# sensor_to_raspi.net
KiCad netlist of a schematic drawn in EAGLE
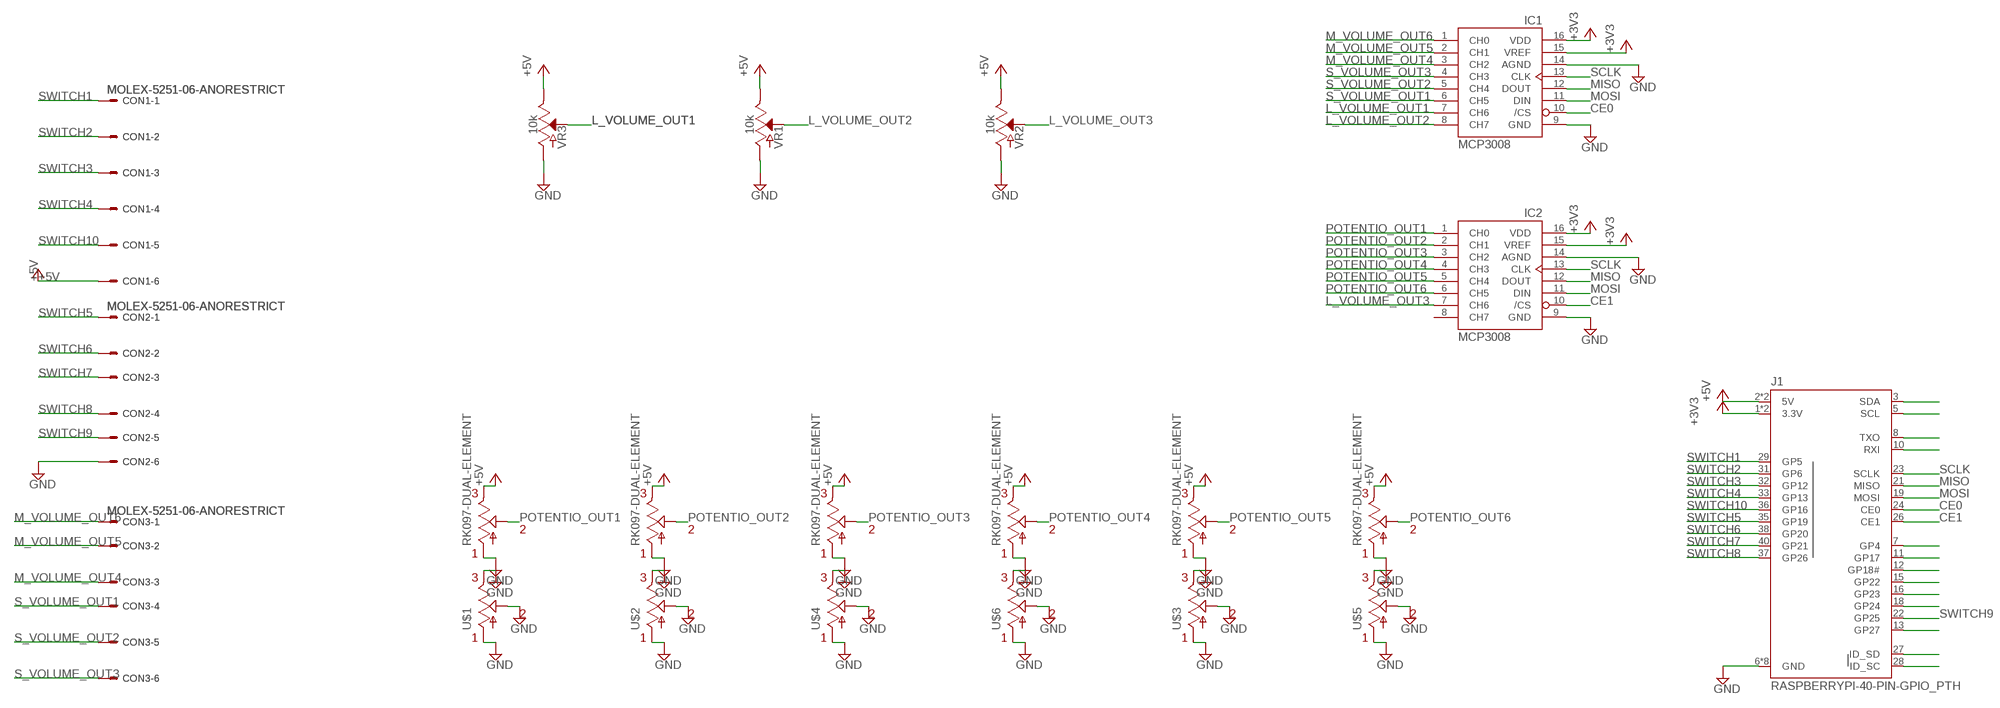
[diagram p0: schematic, sheet 1]

(export (version "E")
  (design (tool "Eeschema 10.0.6"))
  (components
    (comp (ref "CON1")
      (value "MOLEX-5251-06-ANORESTRICT")
      (footprint "eagle-import:5251-06-ANORESTRICT")
      (libsource (lib "eagle-import") (part "MOLEX-5251-06-ANORESTRICT"))
    )
    (comp (ref "CON2")
      (value "MOLEX-5251-06-ANORESTRICT")
      (footprint "eagle-import:5251-06-ANORESTRICT")
      (libsource (lib "eagle-import") (part "MOLEX-5251-06-ANORESTRICT"))
    )
    (comp (ref "CON3")
      (value "MOLEX-5251-06-ANORESTRICT")
      (footprint "eagle-import:5251-06-ANORESTRICT")
      (libsource (lib "eagle-import") (part "MOLEX-5251-06-ANORESTRICT"))
    )
    (comp (ref "IC1")
      (value "MCP3008")
      (footprint "eagle-import:DIL16")
      (libsource (lib "eagle-import") (part "MCP3008"))
    )
    (comp (ref "IC2")
      (value "MCP3008")
      (footprint "eagle-import:DIL16")
      (libsource (lib "eagle-import") (part "MCP3008"))
    )
    (comp (ref "J1")
      (value "RASPBERRYPI-40-PIN-GPIO_PTH")
      (footprint "eagle-import:2X20_SHROUDED")
      (libsource (lib "eagle-import") (part "RASPBERRYPI-40-PIN-GPIO_PTH"))
    )
    (comp (ref "U$1")
      (value "RK097-DUAL-ELEMENT")
      (footprint "eagle-import:RK097-DUAL-ELEMENT")
      (libsource (lib "eagle-import") (part "RK097-DUAL-ELEMENT"))
    )
    (comp (ref "U$2")
      (value "RK097-DUAL-ELEMENT")
      (footprint "eagle-import:RK097-DUAL-ELEMENT")
      (libsource (lib "eagle-import") (part "RK097-DUAL-ELEMENT"))
    )
    (comp (ref "U$3")
      (value "RK097-DUAL-ELEMENT")
      (footprint "eagle-import:RK097-DUAL-ELEMENT")
      (libsource (lib "eagle-import") (part "RK097-DUAL-ELEMENT"))
    )
    (comp (ref "U$4")
      (value "RK097-DUAL-ELEMENT")
      (footprint "eagle-import:RK097-DUAL-ELEMENT")
      (libsource (lib "eagle-import") (part "RK097-DUAL-ELEMENT"))
    )
    (comp (ref "U$5")
      (value "RK097-DUAL-ELEMENT")
      (footprint "eagle-import:RK097-DUAL-ELEMENT")
      (libsource (lib "eagle-import") (part "RK097-DUAL-ELEMENT"))
    )
    (comp (ref "U$6")
      (value "RK097-DUAL-ELEMENT")
      (footprint "eagle-import:RK097-DUAL-ELEMENT")
      (libsource (lib "eagle-import") (part "RK097-DUAL-ELEMENT"))
    )
    (comp (ref "VR1")
      (value "10k")
      (footprint "eagle-import:SLIDER-XLARGE")
      (libsource (lib "eagle-import") (part "POTENTIOMETER_SLIDE-60MM-1/2W-20%"))
    )
    (comp (ref "VR2")
      (value "10k")
      (footprint "eagle-import:SLIDER-XLARGE")
      (libsource (lib "eagle-import") (part "POTENTIOMETER_SLIDE-60MM-1/2W-20%"))
    )
    (comp (ref "VR3")
      (value "10k")
      (footprint "eagle-import:SLIDER-XLARGE")
      (libsource (lib "eagle-import") (part "POTENTIOMETER_SLIDE-60MM-1/2W-20%"))
    )
  )
  (nets
    (net (code "1") (name "+3V3") (class "Default")
      (node (ref "IC1") (pin "15") (pinfunction "VREF_15") (pintype "input"))
      (node (ref "IC1") (pin "16") (pinfunction "VDD_16") (pintype "power_in"))
      (node (ref "IC2") (pin "15") (pinfunction "VREF_15") (pintype "input"))
      (node (ref "IC2") (pin "16") (pinfunction "VDD_16") (pintype "power_in"))
      (node (ref "J1") (pin "1") (pinfunction "3.3V_1") (pintype "power_in"))
      (node (ref "J1") (pin "17") (pinfunction "3.3V_17") (pintype "power_in"))
    )
    (net (code "2") (name "+5V") (class "Default")
      (node (ref "CON1") (pin "6") (pinfunction "S_6") (pintype "passive"))
      (node (ref "J1") (pin "2") (pinfunction "5V_2") (pintype "power_in"))
      (node (ref "J1") (pin "4") (pinfunction "5V_4") (pintype "power_in"))
      (node (ref "U$1") (pin "P$3") (pinfunction "E_P$3") (pintype "passive"))
      (node (ref "U$2") (pin "P$3") (pinfunction "E_P$3") (pintype "passive"))
      (node (ref "U$3") (pin "P$3") (pinfunction "E_P$3") (pintype "passive"))
      (node (ref "U$4") (pin "P$3") (pinfunction "E_P$3") (pintype "passive"))
      (node (ref "U$5") (pin "P$3") (pinfunction "E_P$3") (pintype "passive"))
      (node (ref "U$6") (pin "P$3") (pinfunction "E_P$3") (pintype "passive"))
      (node (ref "VR1") (pin "1") (pinfunction "E_1") (pintype "passive"))
      (node (ref "VR2") (pin "1") (pinfunction "E_1") (pintype "passive"))
      (node (ref "VR3") (pin "1") (pinfunction "E_1") (pintype "passive"))
    )
    (net (code "3") (name "/CE0") (class "Default")
      (node (ref "IC1") (pin "10") (pinfunction "/CS_10") (pintype "input"))
      (node (ref "J1") (pin "24") (pinfunction "CE0_24") (pintype "output"))
    )
    (net (code "4") (name "/CE1") (class "Default")
      (node (ref "IC2") (pin "10") (pinfunction "/CS_10") (pintype "input"))
      (node (ref "J1") (pin "26") (pinfunction "CE1_26") (pintype "output"))
    )
    (net (code "5") (name "/L_VOLUME_OUT1") (class "Default")
      (node (ref "IC1") (pin "7") (pinfunction "CH6_7") (pintype "input"))
      (node (ref "VR3") (pin "2A") (pinfunction "S_2A") (pintype "passive"))
    )
    (net (code "6") (name "/L_VOLUME_OUT2") (class "Default")
      (node (ref "IC1") (pin "8") (pinfunction "CH7_8") (pintype "input"))
      (node (ref "VR1") (pin "2A") (pinfunction "S_2A") (pintype "passive"))
    )
    (net (code "7") (name "/L_VOLUME_OUT3") (class "Default")
      (node (ref "IC2") (pin "7") (pinfunction "CH6_7") (pintype "input"))
      (node (ref "VR2") (pin "2A") (pinfunction "S_2A") (pintype "passive"))
    )
    (net (code "8") (name "/MISO") (class "Default")
      (node (ref "IC1") (pin "12") (pinfunction "DOUT_12") (pintype "output"))
      (node (ref "IC2") (pin "12") (pinfunction "DOUT_12") (pintype "output"))
      (node (ref "J1") (pin "21") (pinfunction "MISO_21") (pintype "input"))
    )
    (net (code "9") (name "/MOSI") (class "Default")
      (node (ref "IC1") (pin "11") (pinfunction "DIN_11") (pintype "input"))
      (node (ref "IC2") (pin "11") (pinfunction "DIN_11") (pintype "input"))
      (node (ref "J1") (pin "19") (pinfunction "MOSI_19") (pintype "output"))
    )
    (net (code "10") (name "/M_VOLUME_OUT4") (class "Default")
      (node (ref "CON3") (pin "3") (pinfunction "S_3") (pintype "passive"))
      (node (ref "IC1") (pin "3") (pinfunction "CH2_3") (pintype "input"))
    )
    (net (code "11") (name "/M_VOLUME_OUT5") (class "Default")
      (node (ref "CON3") (pin "2") (pinfunction "S_2") (pintype "passive"))
      (node (ref "IC1") (pin "2") (pinfunction "CH1_2") (pintype "input"))
    )
    (net (code "12") (name "/M_VOLUME_OUT6") (class "Default")
      (node (ref "CON3") (pin "1") (pinfunction "S_1") (pintype "passive"))
      (node (ref "IC1") (pin "1") (pinfunction "CH0_1") (pintype "input"))
    )
    (net (code "13") (name "/POTENTIO_OUT1") (class "Default")
      (node (ref "IC2") (pin "1") (pinfunction "CH0_1") (pintype "input"))
      (node (ref "U$1") (pin "P$5") (pinfunction "S_P$5") (pintype "passive"))
    )
    (net (code "14") (name "/POTENTIO_OUT2") (class "Default")
      (node (ref "IC2") (pin "2") (pinfunction "CH1_2") (pintype "input"))
      (node (ref "U$2") (pin "P$5") (pinfunction "S_P$5") (pintype "passive"))
    )
    (net (code "15") (name "/POTENTIO_OUT3") (class "Default")
      (node (ref "IC2") (pin "3") (pinfunction "CH2_3") (pintype "input"))
      (node (ref "U$4") (pin "P$5") (pinfunction "S_P$5") (pintype "passive"))
    )
    (net (code "16") (name "/POTENTIO_OUT4") (class "Default")
      (node (ref "IC2") (pin "4") (pinfunction "CH3_4") (pintype "input"))
      (node (ref "U$6") (pin "P$5") (pinfunction "S_P$5") (pintype "passive"))
    )
    (net (code "17") (name "/POTENTIO_OUT5") (class "Default")
      (node (ref "IC2") (pin "5") (pinfunction "CH4_5") (pintype "input"))
      (node (ref "U$3") (pin "P$5") (pinfunction "S_P$5") (pintype "passive"))
    )
    (net (code "18") (name "/POTENTIO_OUT6") (class "Default")
      (node (ref "IC2") (pin "6") (pinfunction "CH5_6") (pintype "input"))
      (node (ref "U$5") (pin "P$5") (pinfunction "S_P$5") (pintype "passive"))
    )
    (net (code "19") (name "/SCLK") (class "Default")
      (node (ref "IC1") (pin "13") (pinfunction "CLK_13") (pintype "input"))
      (node (ref "IC2") (pin "13") (pinfunction "CLK_13") (pintype "input"))
      (node (ref "J1") (pin "23") (pinfunction "SCLK_23") (pintype "output"))
    )
    (net (code "20") (name "/SWITCH1") (class "Default")
      (node (ref "CON1") (pin "1") (pinfunction "S_1") (pintype "passive"))
      (node (ref "J1") (pin "29") (pinfunction "GP5_29") (pintype "bidirectional"))
    )
    (net (code "21") (name "/SWITCH2") (class "Default")
      (node (ref "CON1") (pin "2") (pinfunction "S_2") (pintype "passive"))
      (node (ref "J1") (pin "31") (pinfunction "GP6_31") (pintype "bidirectional"))
    )
    (net (code "22") (name "/SWITCH3") (class "Default")
      (node (ref "CON1") (pin "3") (pinfunction "S_3") (pintype "passive"))
      (node (ref "J1") (pin "32") (pinfunction "GP12_32") (pintype "bidirectional"))
    )
    (net (code "23") (name "/SWITCH4") (class "Default")
      (node (ref "CON1") (pin "4") (pinfunction "S_4") (pintype "passive"))
      (node (ref "J1") (pin "33") (pinfunction "GP13_33") (pintype "bidirectional"))
    )
    (net (code "24") (name "/SWITCH5") (class "Default")
      (node (ref "CON2") (pin "1") (pinfunction "S_1") (pintype "passive"))
      (node (ref "J1") (pin "35") (pinfunction "GP19_35") (pintype "bidirectional"))
    )
    (net (code "25") (name "/SWITCH6") (class "Default")
      (node (ref "CON2") (pin "2") (pinfunction "S_2") (pintype "passive"))
      (node (ref "J1") (pin "38") (pinfunction "GP20_38") (pintype "bidirectional"))
    )
    (net (code "26") (name "/SWITCH7") (class "Default")
      (node (ref "CON2") (pin "3") (pinfunction "S_3") (pintype "passive"))
      (node (ref "J1") (pin "40") (pinfunction "GP21_40") (pintype "bidirectional"))
    )
    (net (code "27") (name "/SWITCH8") (class "Default")
      (node (ref "CON2") (pin "4") (pinfunction "S_4") (pintype "passive"))
      (node (ref "J1") (pin "37") (pinfunction "GP26_37") (pintype "bidirectional"))
    )
    (net (code "28") (name "/SWITCH9") (class "Default")
      (node (ref "CON2") (pin "5") (pinfunction "S_5") (pintype "passive"))
      (node (ref "J1") (pin "22") (pinfunction "GP25_22") (pintype "bidirectional"))
    )
    (net (code "29") (name "/SWITCH10") (class "Default")
      (node (ref "CON1") (pin "5") (pinfunction "S_5") (pintype "passive"))
      (node (ref "J1") (pin "36") (pinfunction "GP16_36") (pintype "bidirectional"))
    )
    (net (code "30") (name "/S_VOLUME_OUT1") (class "Default")
      (node (ref "CON3") (pin "4") (pinfunction "S_4") (pintype "passive"))
      (node (ref "IC1") (pin "6") (pinfunction "CH5_6") (pintype "input"))
    )
    (net (code "31") (name "/S_VOLUME_OUT2") (class "Default")
      (node (ref "CON3") (pin "5") (pinfunction "S_5") (pintype "passive"))
      (node (ref "IC1") (pin "5") (pinfunction "CH4_5") (pintype "input"))
    )
    (net (code "32") (name "/S_VOLUME_OUT3") (class "Default")
      (node (ref "CON3") (pin "6") (pinfunction "S_6") (pintype "passive"))
      (node (ref "IC1") (pin "4") (pinfunction "CH3_4") (pintype "input"))
    )
    (net (code "33") (name "GND") (class "Default")
      (node (ref "CON2") (pin "6") (pinfunction "S_6") (pintype "passive"))
      (node (ref "IC1") (pin "14") (pinfunction "AGND_14") (pintype "power_in"))
      (node (ref "IC1") (pin "9") (pinfunction "GND_9") (pintype "power_in"))
      (node (ref "IC2") (pin "14") (pinfunction "AGND_14") (pintype "power_in"))
      (node (ref "IC2") (pin "9") (pinfunction "GND_9") (pintype "power_in"))
      (node (ref "J1") (pin "14") (pinfunction "GND_14") (pintype "power_in"))
      (node (ref "J1") (pin "20") (pinfunction "GND_20") (pintype "power_in"))
      (node (ref "J1") (pin "25") (pinfunction "GND_25") (pintype "power_in"))
      (node (ref "J1") (pin "30") (pinfunction "GND_30") (pintype "power_in"))
      (node (ref "J1") (pin "34") (pinfunction "GND_34") (pintype "power_in"))
      (node (ref "J1") (pin "39") (pinfunction "GND_39") (pintype "power_in"))
      (node (ref "J1") (pin "6") (pinfunction "GND_6") (pintype "power_in"))
      (node (ref "J1") (pin "9") (pinfunction "GND_9") (pintype "power_in"))
      (node (ref "U$1") (pin "P$1") (pinfunction "A_P$1") (pintype "passive"))
      (node (ref "U$1") (pin "P$2") (pinfunction "A1_P$2") (pintype "passive"))
      (node (ref "U$1") (pin "P$4") (pinfunction "E1_P$4") (pintype "passive"))
      (node (ref "U$1") (pin "P$6") (pinfunction "S1_P$6") (pintype "passive"))
      (node (ref "U$2") (pin "P$1") (pinfunction "A_P$1") (pintype "passive"))
      (node (ref "U$2") (pin "P$2") (pinfunction "A1_P$2") (pintype "passive"))
      (node (ref "U$2") (pin "P$4") (pinfunction "E1_P$4") (pintype "passive"))
      (node (ref "U$2") (pin "P$6") (pinfunction "S1_P$6") (pintype "passive"))
      (node (ref "U$3") (pin "P$1") (pinfunction "A_P$1") (pintype "passive"))
      (node (ref "U$3") (pin "P$2") (pinfunction "A1_P$2") (pintype "passive"))
      (node (ref "U$3") (pin "P$4") (pinfunction "E1_P$4") (pintype "passive"))
      (node (ref "U$3") (pin "P$6") (pinfunction "S1_P$6") (pintype "passive"))
      (node (ref "U$4") (pin "P$1") (pinfunction "A_P$1") (pintype "passive"))
      (node (ref "U$4") (pin "P$2") (pinfunction "A1_P$2") (pintype "passive"))
      (node (ref "U$4") (pin "P$4") (pinfunction "E1_P$4") (pintype "passive"))
      (node (ref "U$4") (pin "P$6") (pinfunction "S1_P$6") (pintype "passive"))
      (node (ref "U$5") (pin "P$1") (pinfunction "A_P$1") (pintype "passive"))
      (node (ref "U$5") (pin "P$2") (pinfunction "A1_P$2") (pintype "passive"))
      (node (ref "U$5") (pin "P$4") (pinfunction "E1_P$4") (pintype "passive"))
      (node (ref "U$5") (pin "P$6") (pinfunction "S1_P$6") (pintype "passive"))
      (node (ref "U$6") (pin "P$1") (pinfunction "A_P$1") (pintype "passive"))
      (node (ref "U$6") (pin "P$2") (pinfunction "A1_P$2") (pintype "passive"))
      (node (ref "U$6") (pin "P$4") (pinfunction "E1_P$4") (pintype "passive"))
      (node (ref "U$6") (pin "P$6") (pinfunction "S1_P$6") (pintype "passive"))
      (node (ref "VR1") (pin "3") (pinfunction "A_3") (pintype "passive"))
      (node (ref "VR2") (pin "3") (pinfunction "A_3") (pintype "passive"))
      (node (ref "VR3") (pin "3") (pinfunction "A_3") (pintype "passive"))
    )
    (net (code "34") (name "unconnected-(IC2-CH7-Pad8)") (class "Default")
      (node (ref "IC2") (pin "8") (pinfunction "CH7_8") (pintype "input"))
    )
    (net (code "35") (name "unconnected-(J1-GP4-Pad7)") (class "Default")
      (node (ref "J1") (pin "7") (pinfunction "GP4_7") (pintype "bidirectional"))
    )
    (net (code "36") (name "unconnected-(J1-GP17-Pad11)") (class "Default")
      (node (ref "J1") (pin "11") (pinfunction "GP17_11") (pintype "bidirectional"))
    )
    (net (code "37") (name "unconnected-(J1-GP18#-Pad12)") (class "Default")
      (node (ref "J1") (pin "12") (pinfunction "GP18#_12") (pintype "bidirectional"))
    )
    (net (code "38") (name "unconnected-(J1-GP22-Pad15)") (class "Default")
      (node (ref "J1") (pin "15") (pinfunction "GP22_15") (pintype "bidirectional"))
    )
    (net (code "39") (name "unconnected-(J1-GP23-Pad16)") (class "Default")
      (node (ref "J1") (pin "16") (pinfunction "GP23_16") (pintype "bidirectional"))
    )
    (net (code "40") (name "unconnected-(J1-GP24-Pad18)") (class "Default")
      (node (ref "J1") (pin "18") (pinfunction "GP24_18") (pintype "bidirectional"))
    )
    (net (code "41") (name "unconnected-(J1-GP27-Pad13)") (class "Default")
      (node (ref "J1") (pin "13") (pinfunction "GP27_13") (pintype "bidirectional"))
    )
    (net (code "42") (name "unconnected-(J1-ID_SC-Pad28)") (class "Default")
      (node (ref "J1") (pin "28") (pinfunction "ID_SC_28") (pintype "bidirectional"))
    )
    (net (code "43") (name "unconnected-(J1-ID_SD-Pad27)") (class "Default")
      (node (ref "J1") (pin "27") (pinfunction "ID_SD_27") (pintype "bidirectional"))
    )
    (net (code "44") (name "unconnected-(J1-RXI-Pad10)") (class "Default")
      (node (ref "J1") (pin "10") (pinfunction "RXI_10") (pintype "input"))
    )
    (net (code "45") (name "unconnected-(J1-SCL-Pad5)") (class "Default")
      (node (ref "J1") (pin "5") (pinfunction "SCL_5") (pintype "bidirectional"))
    )
    (net (code "46") (name "unconnected-(J1-SDA-Pad3)") (class "Default")
      (node (ref "J1") (pin "3") (pinfunction "SDA_3") (pintype "bidirectional"))
    )
    (net (code "47") (name "unconnected-(J1-TXO-Pad8)") (class "Default")
      (node (ref "J1") (pin "8") (pinfunction "TXO_8") (pintype "output"))
    )
  )
)
